# CD_Cap_brd.net
KiCad netlist of a schematic drawn in EAGLE
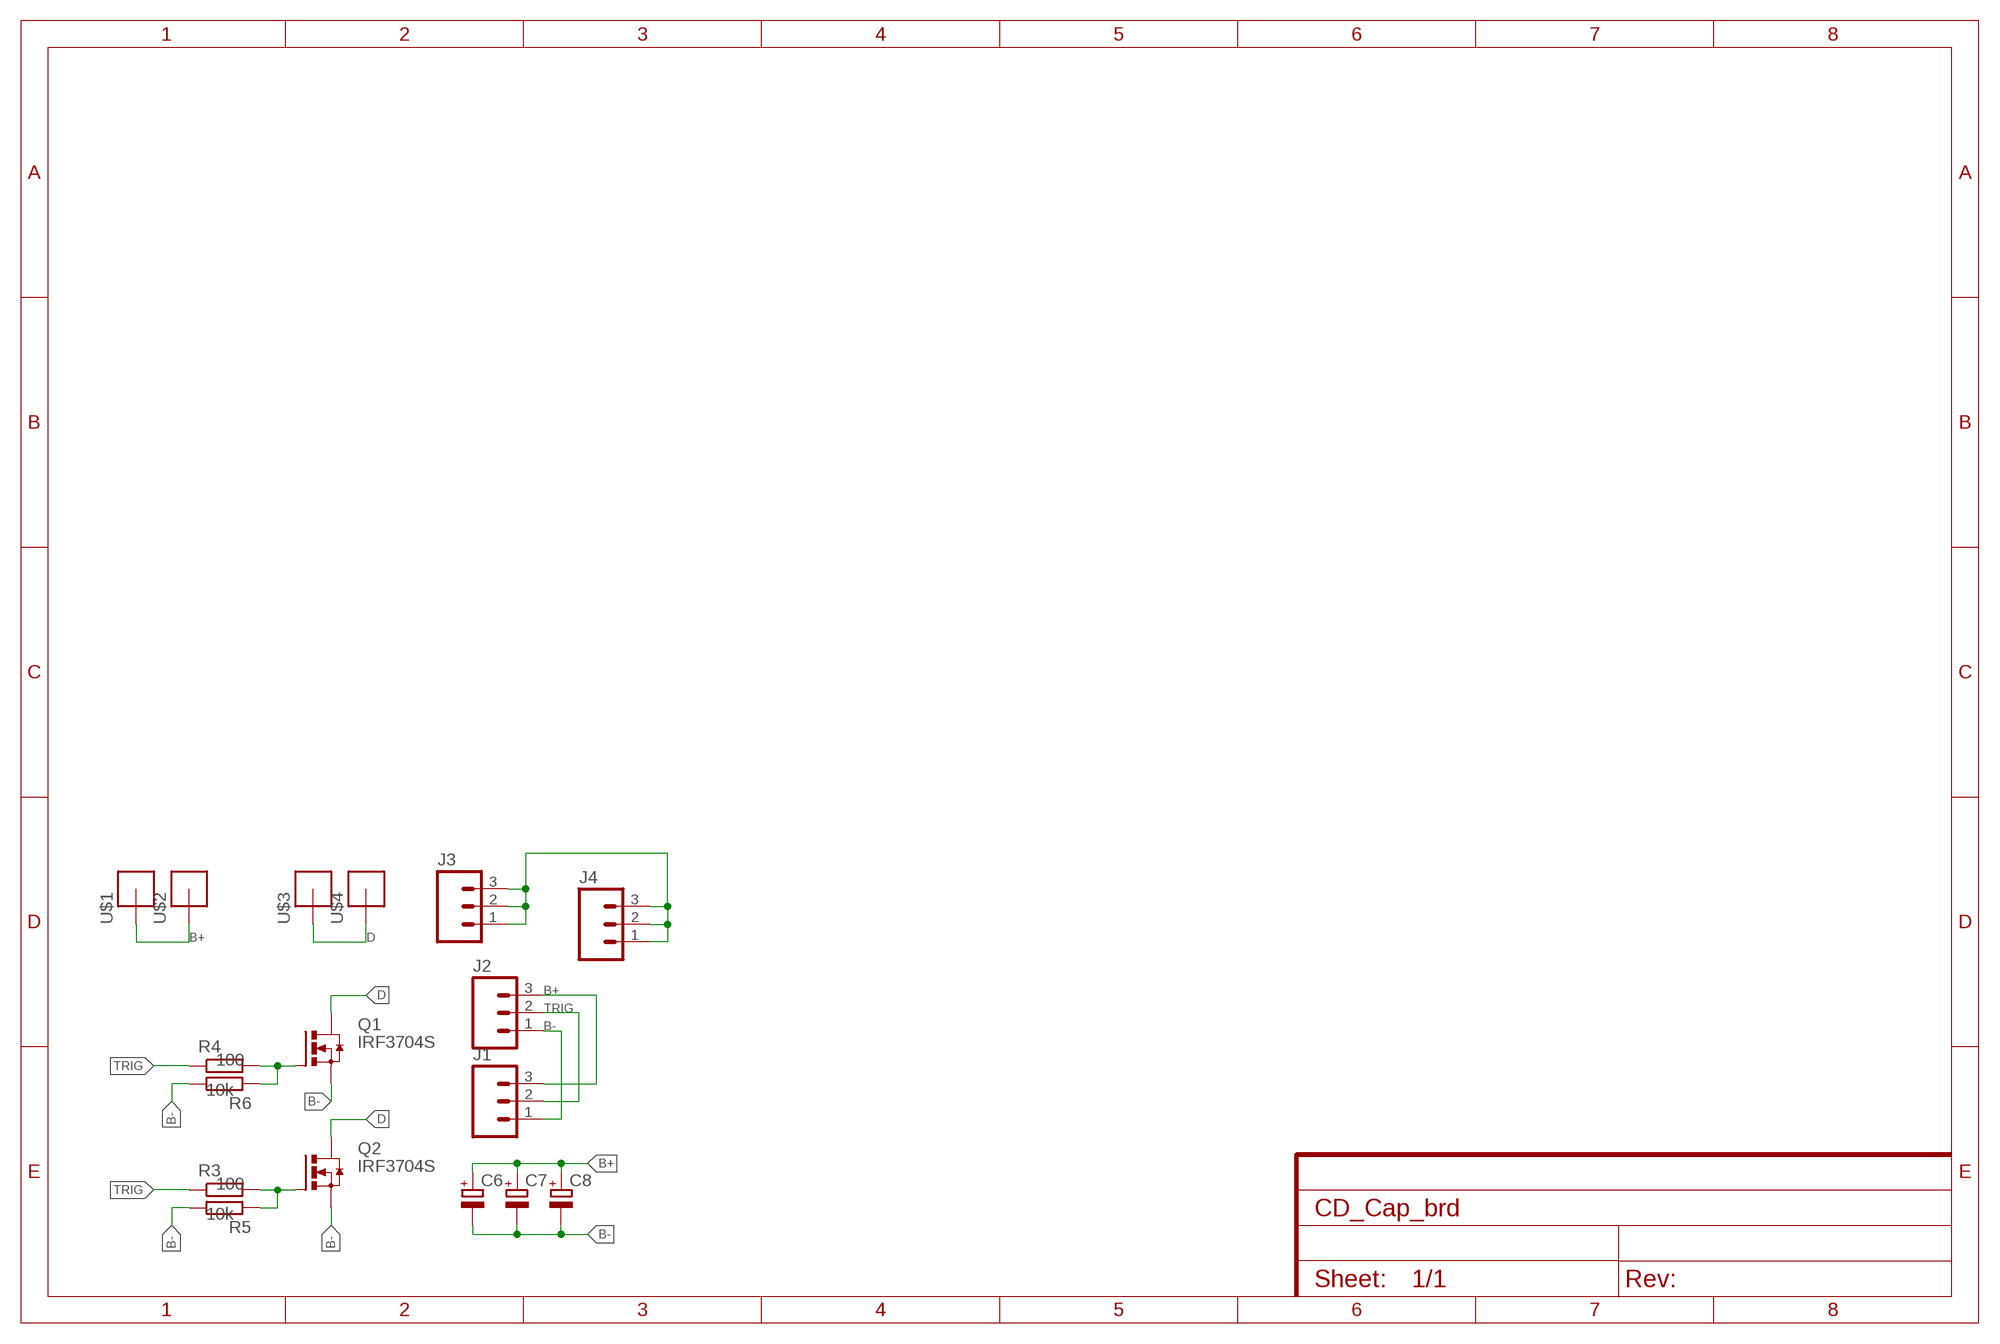
[diagram p0: schematic, sheet 1]

(export (version "E")
  (design (tool "Eeschema 10.0.6"))
  (components
    (comp (ref "C6")
      (value "CPOL-EUE10-35")
      (footprint "eagle-import:EB35D")
      (libsource (lib "eagle-import") (part "CPOL-EUE10-35"))
    )
    (comp (ref "C7")
      (value "CPOL-EUE10-35")
      (footprint "eagle-import:EB35D")
      (libsource (lib "eagle-import") (part "CPOL-EUE10-35"))
    )
    (comp (ref "C8")
      (value "CPOL-EUE10-35")
      (footprint "eagle-import:EB35D")
      (libsource (lib "eagle-import") (part "CPOL-EUE10-35"))
    )
    (comp (ref "J1")
      (value "M03PTH")
      (footprint "eagle-import:1X03")
      (libsource (lib "eagle-import") (part "M03PTH"))
    )
    (comp (ref "J2")
      (value "M03PTH")
      (footprint "eagle-import:1X03")
      (libsource (lib "eagle-import") (part "M03PTH"))
    )
    (comp (ref "J3")
      (value "M03LOCK")
      (footprint "eagle-import:1X03_LOCK")
      (libsource (lib "eagle-import") (part "M03LOCK"))
    )
    (comp (ref "J4")
      (value "M03LOCK")
      (footprint "eagle-import:1X03_LOCK")
      (libsource (lib "eagle-import") (part "M03LOCK"))
    )
    (comp (ref "Q1")
      (value "IRF3704S")
      (footprint "eagle-import:D2PACK")
      (libsource (lib "eagle-import") (part "IRF3704S"))
    )
    (comp (ref "Q2")
      (value "IRF3704S")
      (footprint "eagle-import:D2PACK")
      (libsource (lib "eagle-import") (part "IRF3704S"))
    )
    (comp (ref "R3")
      (value "100")
      (footprint "eagle-import:R0603-N")
      (libsource (lib "eagle-import") (part "RESISTOR0603-N"))
    )
    (comp (ref "R4")
      (value "100")
      (footprint "eagle-import:R0603-N")
      (libsource (lib "eagle-import") (part "RESISTOR0603-N"))
    )
    (comp (ref "R5")
      (value "10k")
      (footprint "eagle-import:R0603-N")
      (libsource (lib "eagle-import") (part "RESISTOR0603-N"))
    )
    (comp (ref "R6")
      (value "10k")
      (footprint "eagle-import:R0603-N")
      (libsource (lib "eagle-import") (part "RESISTOR0603-N"))
    )
    (comp (ref "U$1")
      (value "BIG_PINHEADX110-32")
      (footprint "eagle-import:M6_PINHEAD")
      (libsource (lib "eagle-import") (part "BIG_PINHEADX110-32"))
    )
    (comp (ref "U$2")
      (value "BIG_PINHEADX110-32")
      (footprint "eagle-import:M6_PINHEAD")
      (libsource (lib "eagle-import") (part "BIG_PINHEADX110-32"))
    )
    (comp (ref "U$3")
      (value "BIG_PINHEADX110-32")
      (footprint "eagle-import:M6_PINHEAD")
      (libsource (lib "eagle-import") (part "BIG_PINHEADX110-32"))
    )
    (comp (ref "U$4")
      (value "BIG_PINHEADX110-32")
      (footprint "eagle-import:M6_PINHEAD")
      (libsource (lib "eagle-import") (part "BIG_PINHEADX110-32"))
    )
  )
  (nets
    (net (code "1") (name "B+") (class "Default")
      (node (ref "C6") (pin "+") (pinfunction "+_+") (pintype "passive"))
      (node (ref "C7") (pin "+") (pinfunction "+_+") (pintype "passive"))
      (node (ref "C8") (pin "+") (pinfunction "+_+") (pintype "passive"))
      (node (ref "J1") (pin "3") (pinfunction "3_3") (pintype "passive"))
      (node (ref "J2") (pin "3") (pinfunction "3_3") (pintype "passive"))
      (node (ref "U$1") (pin "P$1") (pinfunction "P$1_P$1") (pintype "bidirectional"))
      (node (ref "U$2") (pin "P$1") (pinfunction "P$1_P$1") (pintype "bidirectional"))
    )
    (net (code "2") (name "B-") (class "Default")
      (node (ref "C6") (pin "-") (pinfunction "-_-") (pintype "passive"))
      (node (ref "C7") (pin "-") (pinfunction "-_-") (pintype "passive"))
      (node (ref "C8") (pin "-") (pinfunction "-_-") (pintype "passive"))
      (node (ref "J1") (pin "1") (pinfunction "1_1") (pintype "passive"))
      (node (ref "J2") (pin "1") (pinfunction "1_1") (pintype "passive"))
      (node (ref "J3") (pin "1") (pinfunction "1_1") (pintype "passive"))
      (node (ref "J3") (pin "2") (pinfunction "2_2") (pintype "passive"))
      (node (ref "J3") (pin "3") (pinfunction "3_3") (pintype "passive"))
      (node (ref "J4") (pin "1") (pinfunction "1_1") (pintype "passive"))
      (node (ref "J4") (pin "2") (pinfunction "2_2") (pintype "passive"))
      (node (ref "J4") (pin "3") (pinfunction "3_3") (pintype "passive"))
      (node (ref "Q1") (pin "3") (pinfunction "S_3") (pintype "passive"))
      (node (ref "Q2") (pin "3") (pinfunction "S_3") (pintype "passive"))
      (node (ref "R5") (pin "2") (pinfunction "P$2_2") (pintype "passive"))
      (node (ref "R6") (pin "2") (pinfunction "P$2_2") (pintype "passive"))
    )
    (net (code "3") (name "D") (class "Default")
      (node (ref "Q1") (pin "2") (pinfunction "D_2") (pintype "passive"))
      (node (ref "Q2") (pin "2") (pinfunction "D_2") (pintype "passive"))
      (node (ref "U$3") (pin "P$1") (pinfunction "P$1_P$1") (pintype "bidirectional"))
      (node (ref "U$4") (pin "P$1") (pinfunction "P$1_P$1") (pintype "bidirectional"))
    )
    (net (code "4") (name "Net-(Q1-G)") (class "Default")
      (node (ref "Q1") (pin "1") (pinfunction "G_1") (pintype "passive"))
      (node (ref "R4") (pin "2") (pinfunction "P$2_2") (pintype "passive"))
      (node (ref "R6") (pin "1") (pinfunction "P$1_1") (pintype "passive"))
    )
    (net (code "5") (name "Net-(Q2-G)") (class "Default")
      (node (ref "Q2") (pin "1") (pinfunction "G_1") (pintype "passive"))
      (node (ref "R3") (pin "2") (pinfunction "P$2_2") (pintype "passive"))
      (node (ref "R5") (pin "1") (pinfunction "P$1_1") (pintype "passive"))
    )
    (net (code "6") (name "TRIG") (class "Default")
      (node (ref "J1") (pin "2") (pinfunction "2_2") (pintype "passive"))
      (node (ref "J2") (pin "2") (pinfunction "2_2") (pintype "passive"))
      (node (ref "R3") (pin "1") (pinfunction "P$1_1") (pintype "passive"))
      (node (ref "R4") (pin "1") (pinfunction "P$1_1") (pintype "passive"))
    )
  )
)
